# TESTEAMPOP.net
KiCad netlist of a schematic drawn in Altium Designer
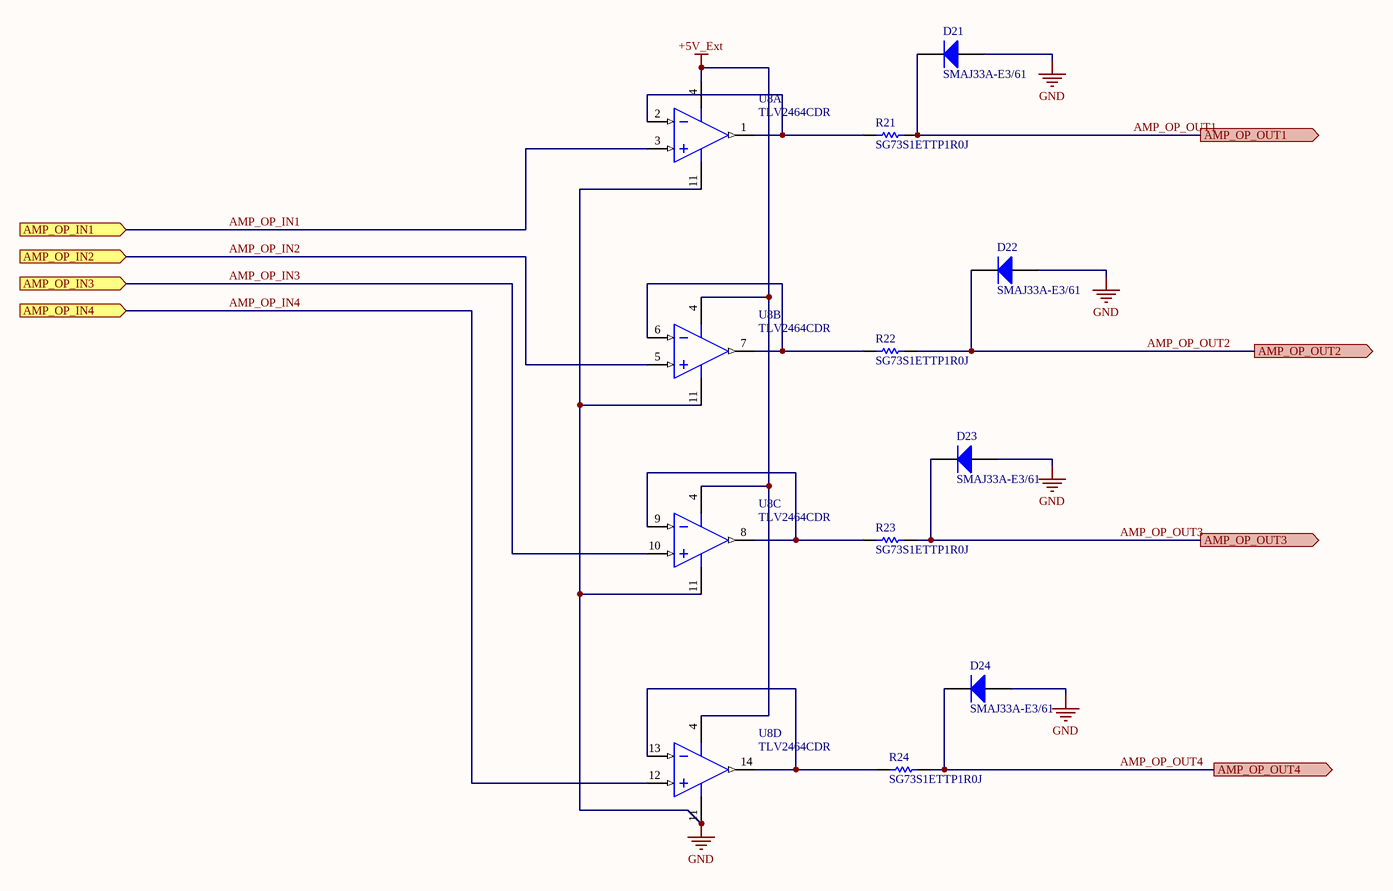
[diagram p0: TESTEAMPOP.SchDoc]

(export (version "E")
  (design (tool "Eeschema 10.0.6"))
  (components
    (comp (ref "D21")
      (value "SMAJ33A-E3/61")
      (footprint "VISH-DO-214AC-2_L")
      (fields (field (name "MANUFACTURER") "Vishay Semiconductor"))
      (libsource (lib "Altium Content Vault") (part "VISH-K1A2-2"))
    )
    (comp (ref "D22")
      (value "SMAJ33A-E3/61")
      (footprint "VISH-DO-214AC-2_L")
      (fields (field (name "MANUFACTURER") "Vishay Semiconductor"))
      (libsource (lib "Altium Content Vault") (part "VISH-K1A2-2"))
    )
    (comp (ref "D23")
      (value "SMAJ33A-E3/61")
      (footprint "VISH-DO-214AC-2_L")
      (fields (field (name "MANUFACTURER") "Vishay Semiconductor"))
      (libsource (lib "Altium Content Vault") (part "VISH-K1A2-2"))
    )
    (comp (ref "D24")
      (value "SMAJ33A-E3/61")
      (footprint "VISH-DO-214AC-2_L")
      (fields (field (name "MANUFACTURER") "Vishay Semiconductor"))
      (libsource (lib "Altium Content Vault") (part "VISH-K1A2-2"))
    )
    (comp (ref "R21")
      (value "SG73S1ETTP1R0J")
      (footprint "RESC1005X40X25LL10T10")
      (fields (field (name "MANUFACTURER") "KOA Speer"))
      (libsource (lib "Altium Content Vault") (part "RES"))
    )
    (comp (ref "R22")
      (value "SG73S1ETTP1R0J")
      (footprint "RESC1005X40X25LL10T10")
      (fields (field (name "MANUFACTURER") "KOA Speer"))
      (libsource (lib "Altium Content Vault") (part "RES"))
    )
    (comp (ref "R23")
      (value "SG73S1ETTP1R0J")
      (footprint "RESC1005X40X25LL10T10")
      (fields (field (name "MANUFACTURER") "KOA Speer"))
      (libsource (lib "Altium Content Vault") (part "RES"))
    )
    (comp (ref "R24")
      (value "SG73S1ETTP1R0J")
      (footprint "RESC1005X40X25LL10T10")
      (fields (field (name "MANUFACTURER") "KOA Speer"))
      (libsource (lib "Altium Content Vault") (part "RES"))
    )
    (comp (ref "U8")
      (value "TLV2464CDR")
      (footprint "D0014A_N")
      (fields (field (name "MANUFACTURER") "Texas Instruments"))
      (libsource (lib "Altium Content Vault") (part "TI-TLV2464X-XX14"))
    )
  )
  (nets
    (net (code "1") (name "+5V_Ext") (class "Default")
      (node (ref "U8") (pin "4") (pinfunction "VDD+_4") (pintype "power_in"))
    )
    (net (code "2") (name "/AMP_OP_IN1") (class "Default")
      (node (ref "U8") (pin "3") (pinfunction "IN1+_3") (pintype "input"))
    )
    (net (code "3") (name "/AMP_OP_IN2") (class "Default")
      (node (ref "U8") (pin "5") (pinfunction "IN2+_5") (pintype "input"))
    )
    (net (code "4") (name "/AMP_OP_IN3") (class "Default")
      (node (ref "U8") (pin "10") (pinfunction "IN3+_10") (pintype "input"))
    )
    (net (code "5") (name "/AMP_OP_IN4") (class "Default")
      (node (ref "U8") (pin "12") (pinfunction "IN4+_12") (pintype "input"))
    )
    (net (code "6") (name "/AMP_OP_OUT1") (class "Default")
      (node (ref "D21") (pin "1") (pinfunction "K_1") (pintype "passive"))
      (node (ref "R21") (pin "2") (pinfunction "2_2") (pintype "passive"))
    )
    (net (code "7") (name "/AMP_OP_OUT2") (class "Default")
      (node (ref "D22") (pin "1") (pinfunction "K_1") (pintype "passive"))
      (node (ref "R22") (pin "2") (pinfunction "2_2") (pintype "passive"))
    )
    (net (code "8") (name "/AMP_OP_OUT3") (class "Default")
      (node (ref "D23") (pin "1") (pinfunction "K_1") (pintype "passive"))
      (node (ref "R23") (pin "2") (pinfunction "2_2") (pintype "passive"))
    )
    (net (code "9") (name "/AMP_OP_OUT4") (class "Default")
      (node (ref "D24") (pin "1") (pinfunction "K_1") (pintype "passive"))
      (node (ref "R24") (pin "2") (pinfunction "2_2") (pintype "passive"))
    )
    (net (code "10") (name "GND") (class "Default")
      (node (ref "D21") (pin "2") (pinfunction "A_2") (pintype "passive"))
      (node (ref "D22") (pin "2") (pinfunction "A_2") (pintype "passive"))
      (node (ref "D23") (pin "2") (pinfunction "A_2") (pintype "passive"))
      (node (ref "D24") (pin "2") (pinfunction "A_2") (pintype "passive"))
      (node (ref "U8") (pin "11") (pinfunction "GND_11") (pintype "power_in"))
    )
    (net (code "11") (name "Net-(U8A-IN1-)") (class "Default")
      (node (ref "R21") (pin "1") (pinfunction "1_1") (pintype "passive"))
      (node (ref "U8") (pin "1") (pinfunction "OUT1_1") (pintype "output"))
      (node (ref "U8") (pin "2") (pinfunction "IN1-_2") (pintype "input"))
    )
    (net (code "12") (name "Net-(U8B-IN2-)") (class "Default")
      (node (ref "R22") (pin "1") (pinfunction "1_1") (pintype "passive"))
      (node (ref "U8") (pin "6") (pinfunction "IN2-_6") (pintype "input"))
      (node (ref "U8") (pin "7") (pinfunction "OUT2_7") (pintype "output"))
    )
    (net (code "13") (name "Net-(U8C-IN3-)") (class "Default")
      (node (ref "R23") (pin "1") (pinfunction "1_1") (pintype "passive"))
      (node (ref "U8") (pin "8") (pinfunction "OUT3_8") (pintype "output"))
      (node (ref "U8") (pin "9") (pinfunction "IN3-_9") (pintype "input"))
    )
    (net (code "14") (name "Net-(U8D-IN4-)") (class "Default")
      (node (ref "R24") (pin "1") (pinfunction "1_1") (pintype "passive"))
      (node (ref "U8") (pin "13") (pinfunction "IN4-_13") (pintype "input"))
      (node (ref "U8") (pin "14") (pinfunction "OUT4_14") (pintype "output"))
    )
  )
)
